# bqZUM_Power.net
KiCad netlist of a schematic drawn in Altium Designer
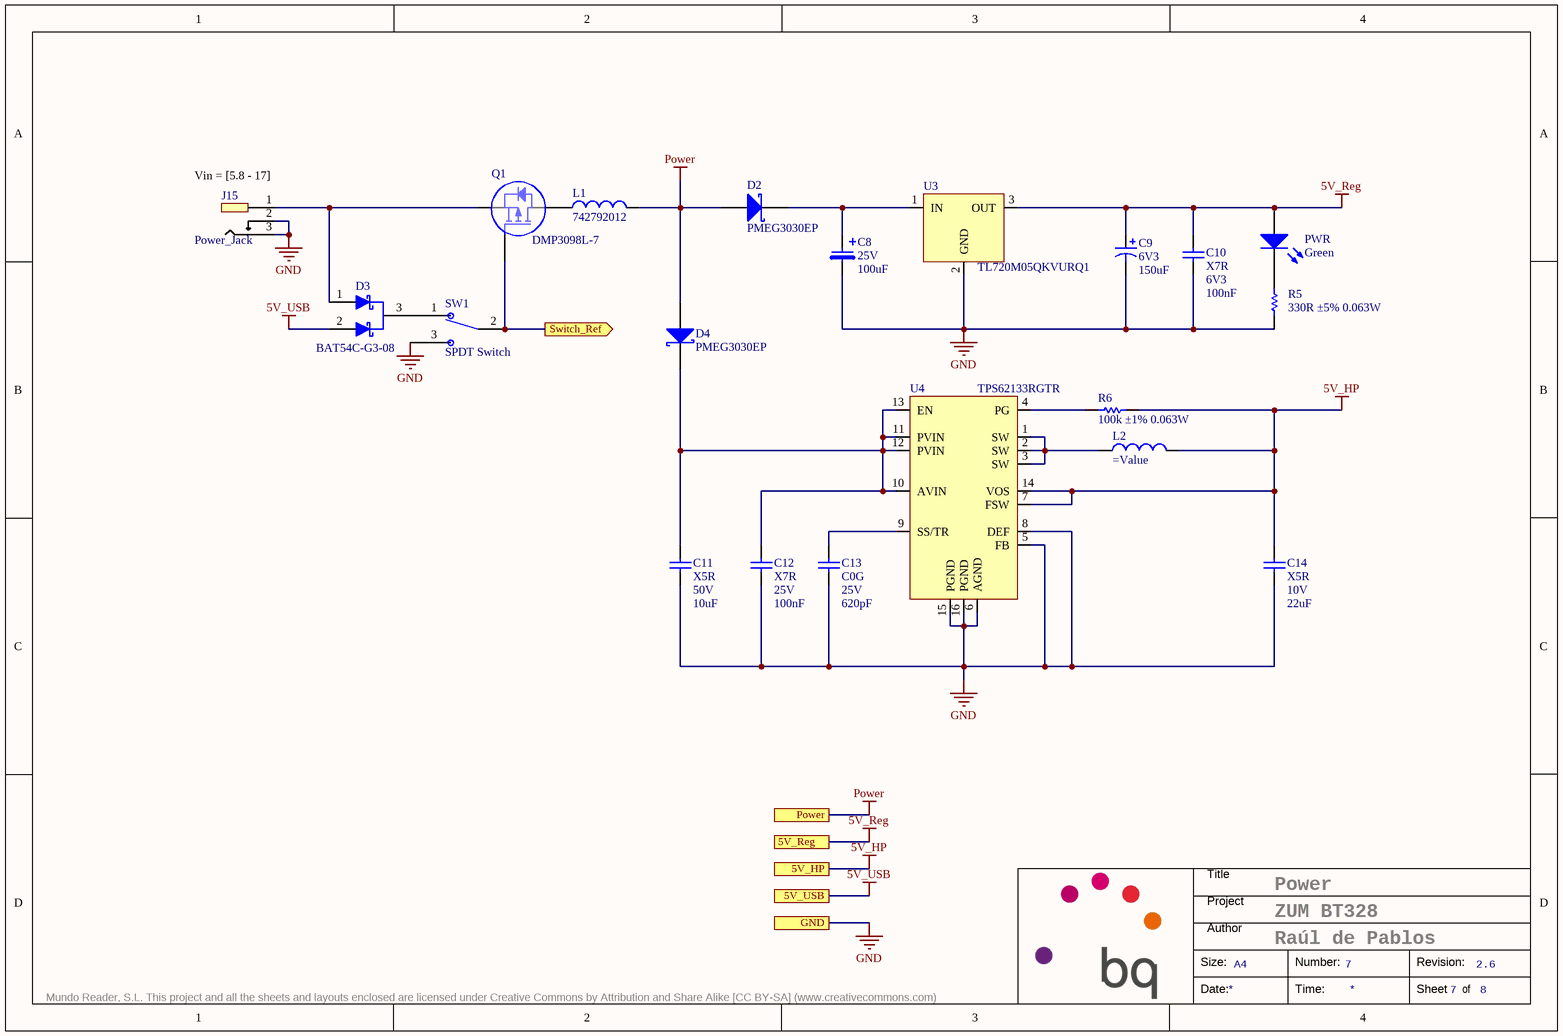
[diagram p0: bqZUM_Power.SchDoc]

(export (version "E")
  (design (tool "Eeschema 10.0.6"))
  (components
    (comp (ref "C8")
      (value "Electrolytic")
      (footprint "CASE_D_7.7")
      (description "Capacitor Electrolytic")
      (fields
        (field (name "VOLTAGE") "25V")
        (field (name "CAPACITANCE") "100uF")
        (field (name "PART NUMBER") "Cap_Al_100uF_25V")
        (field (name "MANUFACTURER") "Panasonic")
      )
      (libsource (lib "Pasives_Electrolytic_SMD") (part "Electrolytic"))
    )
    (comp (ref "C9")
      (value "Tantalum")
      (footprint "CASE_B_3528-1411")
      (description "Tantalum Capacitor")
      (fields
        (field (name "VOLTAGE") "6V3")
        (field (name "CAPACITANCE") "150uF")
        (field (name "PART NUMBER") "150uF_6V3_±20%")
        (field (name "TOLERANCE") "±20%")
      )
      (libsource (lib "Pasives_Tantal_SMD") (part "Tantalum"))
    )
    (comp (ref "C10")
      (value "Capacitor")
      (footprint "C0402")
      (fields
        (field (name "DIELECTRIC") "X7R")
        (field (name "VOLTAGE") "6V3")
        (field (name "CAPACITANCE") "100nF")
        (field (name "PART NUMBER") "C0402_100nF_6V3_±10%")
        (field (name "TOLERANCE") "±10%")
        (field (name "MANUFACTURER") "Kemet")
      )
      (libsource (lib "Pasives_Capacitor_SMD") (part "Capacitor"))
    )
    (comp (ref "C11")
      (value "Capacitor")
      (footprint "C1206")
      (fields
        (field (name "DIELECTRIC") "X5R")
        (field (name "VOLTAGE") "50V")
        (field (name "CAPACITANCE") "10uF")
        (field (name "PART NUMBER") "C1206_10uF_50V_±20%")
        (field (name "TOLERANCE") "±20%")
        (field (name "MANUFACTURER") "Taiyo Yuden")
      )
      (libsource (lib "Pasives_Capacitor_SMD") (part "Capacitor"))
    )
    (comp (ref "C12")
      (value "Capacitor")
      (footprint "C0603")
      (fields
        (field (name "DIELECTRIC") "X7R")
        (field (name "VOLTAGE") "25V")
        (field (name "CAPACITANCE") "100nF")
        (field (name "PART NUMBER") "C0603_100nF_25V_±10%")
        (field (name "TOLERANCE") "±10%")
        (field (name "MANUFACTURER") "Kemet")
      )
      (libsource (lib "Pasives_Capacitor_SMD") (part "Capacitor"))
    )
    (comp (ref "C13")
      (value "Capacitor")
      (footprint "C0603")
      (fields
        (field (name "DIELECTRIC") "C0G")
        (field (name "VOLTAGE") "25V")
        (field (name "CAPACITANCE") "620pF")
        (field (name "PART NUMBER") "C0603_620pF_25V_±5%")
        (field (name "TOLERANCE") "±5%")
        (field (name "MANUFACTURER") "Murata")
      )
      (libsource (lib "Pasives_Capacitor_SMD") (part "Capacitor"))
    )
    (comp (ref "C14")
      (value "Capacitor")
      (footprint "C1206")
      (fields
        (field (name "DIELECTRIC") "X5R")
        (field (name "VOLTAGE") "10V")
        (field (name "CAPACITANCE") "22uF")
        (field (name "PART NUMBER") "C1206_22uF_10V_±20%")
        (field (name "TOLERANCE") "±20%")
        (field (name "MANUFACTURER") "Taiyo Yuden")
      )
      (libsource (lib "Pasives_Capacitor_SMD") (part "Capacitor"))
    )
    (comp (ref "D2")
      (value "PMEG3030EP")
      (footprint "SOD128")
      (description "Diodo Schottky")
      (fields (field (name "MANUFACTURER") "NXP"))
      (libsource (lib "Semiconductors_Diodes") (part "Schottky"))
    )
    (comp (ref "D3")
      (value "BAT54C-G3-08")
      (footprint "SOT23-3")
      (description "Dual Schottky Diode Common Cathode")
      (fields (field (name "PART NUMBER") "BAT54C") (field (name "MANUFACTURER") "Vishay"))
      (libsource (lib "Semiconductors_Diodes") (part "Dual_Diode_Schottky_BAT54C"))
    )
    (comp (ref "D4")
      (value "PMEG3030EP")
      (footprint "SOD128")
      (description "Diodo Schottky")
      (fields (field (name "MANUFACTURER") "NXP"))
      (libsource (lib "Semiconductors_Diodes") (part "Schottky"))
    )
    (comp (ref "J15")
      (value "Power_Jack")
      (footprint "Jack 2.1")
      (description "DC Power Jack")
      (fields (field (name "MANUFACTURER") "Kycon"))
      (libsource (lib "Connectors_Power") (part "Power_Jack"))
    )
    (comp (ref "L1")
      (value "742792012")
      (footprint "L0805")
      (description "Ferrite Bead")
      (fields
        (field (name "PART NUMBER") "L0805_33R_0,008R_4000mA")
        (field (name "MANUFACTURER") "Würth Elektronik")
      )
      (libsource (lib "Pasivos_Inductor_SMD") (part "Ferrite Bead"))
    )
    (comp (ref "L2")
      (value "~")
      (footprint "SRN8040")
      (description "Inductor SMD")
      (fields (field (name "PART NUMBER") "2,2uH_6,3A") (field (name "MANUFACTURER") "Bourns"))
      (libsource (lib "Pasivos_Inductor_SMD") (part "Inductor"))
    )
    (comp (ref "PWR")
      (value "Green")
      (footprint "LED0603")
      (description "Light Emitting Diode")
      (fields (field (name "PART NUMBER") "LG Q971-KN-1") (field (name "MANUFACTURER") "OSRAM Opto"))
      (libsource (lib "Optoelectronics") (part "LED"))
    )
    (comp (ref "Q1")
      (value "DMP3098L-7")
      (footprint "SOT23-3")
      (description "Mosfet Channel P Enhancement Mode")
      (fields (field (name "PART NUMBER") "DMP3098L") (field (name "MANUFACTURER") "Diodes Incorporated"))
      (libsource (lib "Semiconductors_Transistors") (part "Mosfet_P"))
    )
    (comp (ref "R5")
      (value "330R ±5% 0.063W")
      (footprint "R0402")
      (description "Resistor")
      (fields (field (name "TOLERANCE") "±5%") (field (name "POWER") "0.063W"))
      (libsource (lib "Pasives_Resistor_SMD") (part "Resistor"))
    )
    (comp (ref "R6")
      (value "100k ±1% 0.063W")
      (footprint "R0402")
      (description "Resistor")
      (fields (field (name "TOLERANCE") "±1%") (field (name "POWER") "0.063W"))
      (libsource (lib "Pasives_Resistor_SMD") (part "Resistor"))
    )
    (comp (ref "SW1")
      (value "SPDT Switch")
      (footprint "Slide SW SPDT Right Angle")
      (fields (field (name "PART NUMBER") "Switch SPDT") (field (name "MANUFACTURER") "Würth Elektronik"))
      (libsource (lib "Electromechanical") (part "SPDT Switch"))
    )
    (comp (ref "U3")
      (value "TL720M05QKVURQ1")
      (footprint "TO-252")
      (description "Standard 3pin LDO")
      (fields (field (name "PART NUMBER") "TL720M05-Q1") (field (name "MANUFACTURER") "Texas Instruments"))
      (libsource (lib "Power_Regulator") (part "LDO-3"))
    )
    (comp (ref "U4")
      (value "TPS62133RGTR")
      (footprint "QFN16")
      (description "3A High Efficient Synchronous Step Down Converter with DCS™ Control")
      (fields (field (name "PART NUMBER") "TPS62133") (field (name "MANUFACTURER") "Texas Instruments"))
      (libsource (lib "Power_Regulator") (part "TPS6213x"))
    )
  )
  (nets
    (net (code "1") (name "/Switch_Ref") (class "Default")
      (node (ref "Q1") (pin "1") (pinfunction "G_1") (pintype "passive"))
      (node (ref "SW1") (pin "2") (pinfunction "2_2") (pintype "passive"))
    )
    (net (code "2") (name "5V_HP") (class "Default")
      (node (ref "C14") (pin "2") (pinfunction "2_2") (pintype "passive"))
      (node (ref "L2") (pin "2") (pinfunction "2_2") (pintype "passive"))
      (node (ref "R6") (pin "2") (pinfunction "2_2") (pintype "passive"))
      (node (ref "U4") (pin "14") (pinfunction "VOS_14") (pintype "passive"))
      (node (ref "U4") (pin "7") (pinfunction "FSW_7") (pintype "passive"))
    )
    (net (code "3") (name "5V_Reg") (class "Default")
      (node (ref "C10") (pin "2") (pinfunction "2_2") (pintype "passive"))
      (node (ref "C9") (pin "1") (pinfunction "1_1") (pintype "passive"))
      (node (ref "PWR") (pin "A") (pinfunction "A_A") (pintype "passive"))
      (node (ref "U3") (pin "3") (pinfunction "OUT_3") (pintype "passive"))
    )
    (net (code "4") (name "5V_USB") (class "Default")
      (node (ref "D3") (pin "2") (pinfunction "A2_2") (pintype "passive"))
    )
    (net (code "5") (name "GND") (class "Default")
      (node (ref "C10") (pin "1") (pinfunction "1_1") (pintype "passive"))
      (node (ref "C11") (pin "1") (pinfunction "1_1") (pintype "passive"))
      (node (ref "C12") (pin "1") (pinfunction "1_1") (pintype "passive"))
      (node (ref "C13") (pin "1") (pinfunction "1_1") (pintype "passive"))
      (node (ref "C14") (pin "1") (pinfunction "1_1") (pintype "passive"))
      (node (ref "C8") (pin "2") (pinfunction "2_2") (pintype "passive"))
      (node (ref "C9") (pin "2") (pinfunction "2_2") (pintype "passive"))
      (node (ref "J15") (pin "2") (pinfunction "2_2") (pintype "passive"))
      (node (ref "J15") (pin "3") (pinfunction "3_3") (pintype "passive"))
      (node (ref "R5") (pin "1") (pinfunction "1_1") (pintype "passive"))
      (node (ref "SW1") (pin "3") (pinfunction "3_3") (pintype "passive"))
      (node (ref "U3") (pin "2") (pinfunction "GND_2") (pintype "passive"))
      (node (ref "U4") (pin "15") (pinfunction "PGND_15") (pintype "passive"))
      (node (ref "U4") (pin "16") (pinfunction "PGND_16") (pintype "passive"))
      (node (ref "U4") (pin "5") (pinfunction "FB_5") (pintype "passive"))
      (node (ref "U4") (pin "6") (pinfunction "AGND_6") (pintype "passive"))
      (node (ref "U4") (pin "8") (pinfunction "DEF_8") (pintype "passive"))
    )
    (net (code "6") (name "Net-(D2-K)") (class "Default")
      (node (ref "C8") (pin "1") (pinfunction "1_1") (pintype "passive"))
      (node (ref "D2") (pin "k") (pinfunction "K_k") (pintype "passive"))
      (node (ref "U3") (pin "1") (pinfunction "IN_1") (pintype "passive"))
    )
    (net (code "7") (name "Net-(D3-A1)") (class "Default")
      (node (ref "D3") (pin "1") (pinfunction "A1_1") (pintype "passive"))
      (node (ref "J15") (pin "1") (pinfunction "1_1") (pintype "passive"))
      (node (ref "Q1") (pin "2") (pinfunction "S_2") (pintype "passive"))
    )
    (net (code "8") (name "Net-(D3-K)") (class "Default")
      (node (ref "D3") (pin "3") (pinfunction "K_3") (pintype "passive"))
      (node (ref "SW1") (pin "1") (pinfunction "1_1") (pintype "passive"))
    )
    (net (code "9") (name "Net-(D4-K)") (class "Default")
      (node (ref "C11") (pin "2") (pinfunction "2_2") (pintype "passive"))
      (node (ref "C12") (pin "2") (pinfunction "2_2") (pintype "passive"))
      (node (ref "D4") (pin "k") (pinfunction "K_k") (pintype "passive"))
      (node (ref "U4") (pin "10") (pinfunction "AVIN_10") (pintype "passive"))
      (node (ref "U4") (pin "11") (pinfunction "PVIN_11") (pintype "passive"))
      (node (ref "U4") (pin "12") (pinfunction "PVIN_12") (pintype "passive"))
      (node (ref "U4") (pin "13") (pinfunction "EN_13") (pintype "passive"))
    )
    (net (code "10") (name "Net-(L2-Pad1)") (class "Default")
      (node (ref "L2") (pin "1") (pinfunction "1_1") (pintype "passive"))
      (node (ref "U4") (pin "1") (pinfunction "SW_1") (pintype "passive"))
      (node (ref "U4") (pin "2") (pinfunction "SW_2") (pintype "passive"))
      (node (ref "U4") (pin "3") (pinfunction "SW_3") (pintype "passive"))
    )
    (net (code "11") (name "Net-(PWR-PadK)") (class "Default")
      (node (ref "PWR") (pin "K") (pinfunction "K_K") (pintype "passive"))
      (node (ref "R5") (pin "2") (pinfunction "2_2") (pintype "passive"))
    )
    (net (code "12") (name "Net-(Q1-D)") (class "Default")
      (node (ref "L1") (pin "1") (pinfunction "1_1") (pintype "passive"))
      (node (ref "Q1") (pin "3") (pinfunction "D_3") (pintype "passive"))
    )
    (net (code "13") (name "Net-(U4-PG)") (class "Default")
      (node (ref "R6") (pin "1") (pinfunction "1_1") (pintype "passive"))
      (node (ref "U4") (pin "4") (pinfunction "PG_4") (pintype "passive"))
    )
    (net (code "14") (name "Net-(U4-SS{slash}TR)") (class "Default")
      (node (ref "C13") (pin "2") (pinfunction "2_2") (pintype "passive"))
      (node (ref "U4") (pin "9") (pinfunction "SS/TR_9") (pintype "passive"))
    )
    (net (code "15") (name "Power") (class "Default")
      (node (ref "D2") (pin "A") (pinfunction "A_A") (pintype "passive"))
      (node (ref "D4") (pin "A") (pinfunction "A_A") (pintype "passive"))
      (node (ref "L1") (pin "2") (pinfunction "2_2") (pintype "passive"))
    )
  )
)
